# EIT_Teensy_DDS.net
KiCad netlist of a schematic drawn in Altium Designer
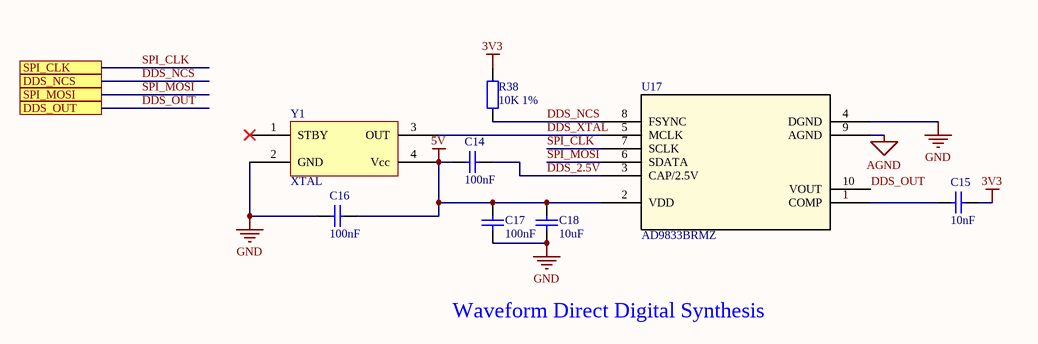
[diagram p0: EIT_Teensy_DDS.SchDoc]

(export (version "E")
  (design (tool "Eeschema 10.0.6"))
  (components
    (comp (ref "C14")
      (value "100nF")
      (footprint "0603 CAP")
      (description "Multi Layer Ceramic Capacitor (MLCC) / Cap Ceramic 0.1uF 50V X7R 10% Pad SMD 0603 125°C T/R")
      (fields
        (field (name "MANUFACTURER") "Samsung")
        (field (name "MANUFACTURER PART NUMBER") "CL10B104KB8NNNC")
      )
      (libsource (lib "EitLib") (part "Cap 0603 100nF 10% 50V"))
    )
    (comp (ref "C15")
      (value "10nF")
      (footprint "0603 CAP")
      (description "CAP CER 10000PF 50V X7R 0603")
      (fields
        (field (name "MANUFACTURER") "Samsung")
        (field (name "MANUFACTURER PART NUMBER") "CL10B103KB8NFNC")
      )
      (libsource (lib "EitLib") (part "Cap 0603 10nF 10% 50V"))
    )
    (comp (ref "C16")
      (value "100nF")
      (footprint "0603 CAP")
      (description "Multi Layer Ceramic Capacitor (MLCC) / Cap Ceramic 0.1uF 50V X7R 10% Pad SMD 0603 125°C T/R")
      (fields
        (field (name "MANUFACTURER") "Samsung")
        (field (name "MANUFACTURER PART NUMBER") "CL10B104KB8NNNC")
      )
      (libsource (lib "EitLib") (part "Cap 0603 100nF 10% 50V"))
    )
    (comp (ref "C17")
      (value "100nF")
      (footprint "0603 CAP")
      (description "Multi Layer Ceramic Capacitor (MLCC) / Cap Ceramic 0.1uF 50V X7R 10% Pad SMD 0603 125°C T/R")
      (fields
        (field (name "MANUFACTURER") "Samsung")
        (field (name "MANUFACTURER PART NUMBER") "CL10B104KB8NNNC")
      )
      (libsource (lib "EitLib") (part "Cap 0603 100nF 10% 50V"))
    )
    (comp (ref "C18")
      (value "10uF")
      (footprint "0603 CAP")
      (description "0603 10 uF 25 V ±20 % Tolerance X5R Surface Mount Multilayer Ceramic Capacitor")
      (fields
        (field (name "MANUFACTURER") "Murata")
        (field (name "MANUFACTURER PART NUMBER") "GRT188R61E106ME13D")
      )
      (libsource (lib "EitLib") (part "Cap 0603 10uF 10% 25V"))
    )
    (comp (ref "R38")
      (value "10K 1%")
      (footprint "0603 RES")
      (description "Res General Purpose Thick Film 0603 10K Ohm 1% 1/10W ±100ppm/°C Molded SMD Paper T/R")
      (fields
        (field (name "MANUFACTURER") "Yageo")
        (field (name "MANUFACTURER PART NUMBER") "RC0603FR-0710KL")
      )
      (libsource (lib "EitLib") (part "Res 0603 10K 1%"))
    )
    (comp (ref "U17")
      (value "AD9833BRMZ")
      (footprint "RM_10_ADI")
      (description "Direct Digital Synthesizer 25MHz 1-DAC 10-Bit Serial 10-Pin MSOP T/R")
      (fields
        (field (name "MANUFACTURER") "Analog Devices")
        (field (name "MANUFACTURER PART NUMBER") "AD9833BRMZ-REEL")
      )
      (libsource (lib "EitLib") (part "AD9833BRMZ"))
    )
    (comp (ref "Y1")
      (value "XTAL")
      (footprint "XTAL SMD")
      (fields
        (field (name "MANUFACTURER") "Abracon")
        (field (name "MANUFACTURER PART NUMBER") "ABM3B-16.000MHZ-B2-T")
        (field (name "TOLERANCE") "20ppm")
      )
      (libsource (lib "EitLib") (part "XTAL 16MHz 5V SMD"))
    )
  )
  (nets
    (net (code "1") (name "/DDS_2.5V") (class "Default")
      (node (ref "C14") (pin "2") (pinfunction "2_2") (pintype "passive"))
      (node (ref "U17") (pin "3") (pinfunction "CAP/2.5V_3") (pintype "power_in"))
    )
    (net (code "2") (name "/DDS_NCS") (class "Default")
      (node (ref "R38") (pin "1") (pinfunction "1_1") (pintype "passive"))
      (node (ref "U17") (pin "8") (pinfunction "FSYNC_8") (pintype "passive"))
    )
    (net (code "3") (name "/DDS_OUT") (class "Default")
      (node (ref "U17") (pin "10") (pinfunction "VOUT_10") (pintype "passive"))
    )
    (net (code "4") (name "/DDS_XTAL") (class "Default")
      (node (ref "U17") (pin "5") (pinfunction "MCLK_5") (pintype "passive"))
      (node (ref "Y1") (pin "3") (pinfunction "OUT_3") (pintype "passive"))
    )
    (net (code "5") (name "/SPI_CLK") (class "Default")
      (node (ref "U17") (pin "7") (pinfunction "SCLK_7") (pintype "passive"))
    )
    (net (code "6") (name "/SPI_MOSI") (class "Default")
      (node (ref "U17") (pin "6") (pinfunction "SDATA_6") (pintype "passive"))
    )
    (net (code "7") (name "3V3") (class "Default")
      (node (ref "C15") (pin "2") (pinfunction "2_2") (pintype "passive"))
      (node (ref "R38") (pin "2") (pinfunction "2_2") (pintype "passive"))
    )
    (net (code "8") (name "5V") (class "Default")
      (node (ref "C14") (pin "1") (pinfunction "1_1") (pintype "passive"))
      (node (ref "C16") (pin "1") (pinfunction "1_1") (pintype "passive"))
      (node (ref "C17") (pin "2") (pinfunction "2_2") (pintype "passive"))
      (node (ref "C18") (pin "2") (pinfunction "2_2") (pintype "passive"))
      (node (ref "U17") (pin "2") (pinfunction "VDD_2") (pintype "power_in"))
      (node (ref "Y1") (pin "4") (pinfunction "Vcc_4") (pintype "passive"))
    )
    (net (code "9") (name "AGND") (class "Default")
      (node (ref "U17") (pin "9") (pinfunction "AGND_9") (pintype "passive"))
    )
    (net (code "10") (name "GND") (class "Default")
      (node (ref "C16") (pin "2") (pinfunction "2_2") (pintype "passive"))
      (node (ref "C17") (pin "1") (pinfunction "1_1") (pintype "passive"))
      (node (ref "C18") (pin "1") (pinfunction "1_1") (pintype "passive"))
      (node (ref "U17") (pin "4") (pinfunction "DGND_4") (pintype "passive"))
      (node (ref "Y1") (pin "2") (pinfunction "GND_2") (pintype "passive"))
    )
    (net (code "11") (name "Net-(U17-COMP)") (class "Default")
      (node (ref "C15") (pin "1") (pinfunction "1_1") (pintype "passive"))
      (node (ref "U17") (pin "1") (pinfunction "COMP_1") (pintype "passive"))
    )
    (net (code "12") (name "unconnected-(Y1-STBY-Pad1)") (class "Default")
      (node (ref "Y1") (pin "1") (pinfunction "STBY_1") (pintype "passive+no_connect"))
    )
  )
)
